# MCU.net
KiCad netlist of a schematic drawn in Altium Designer
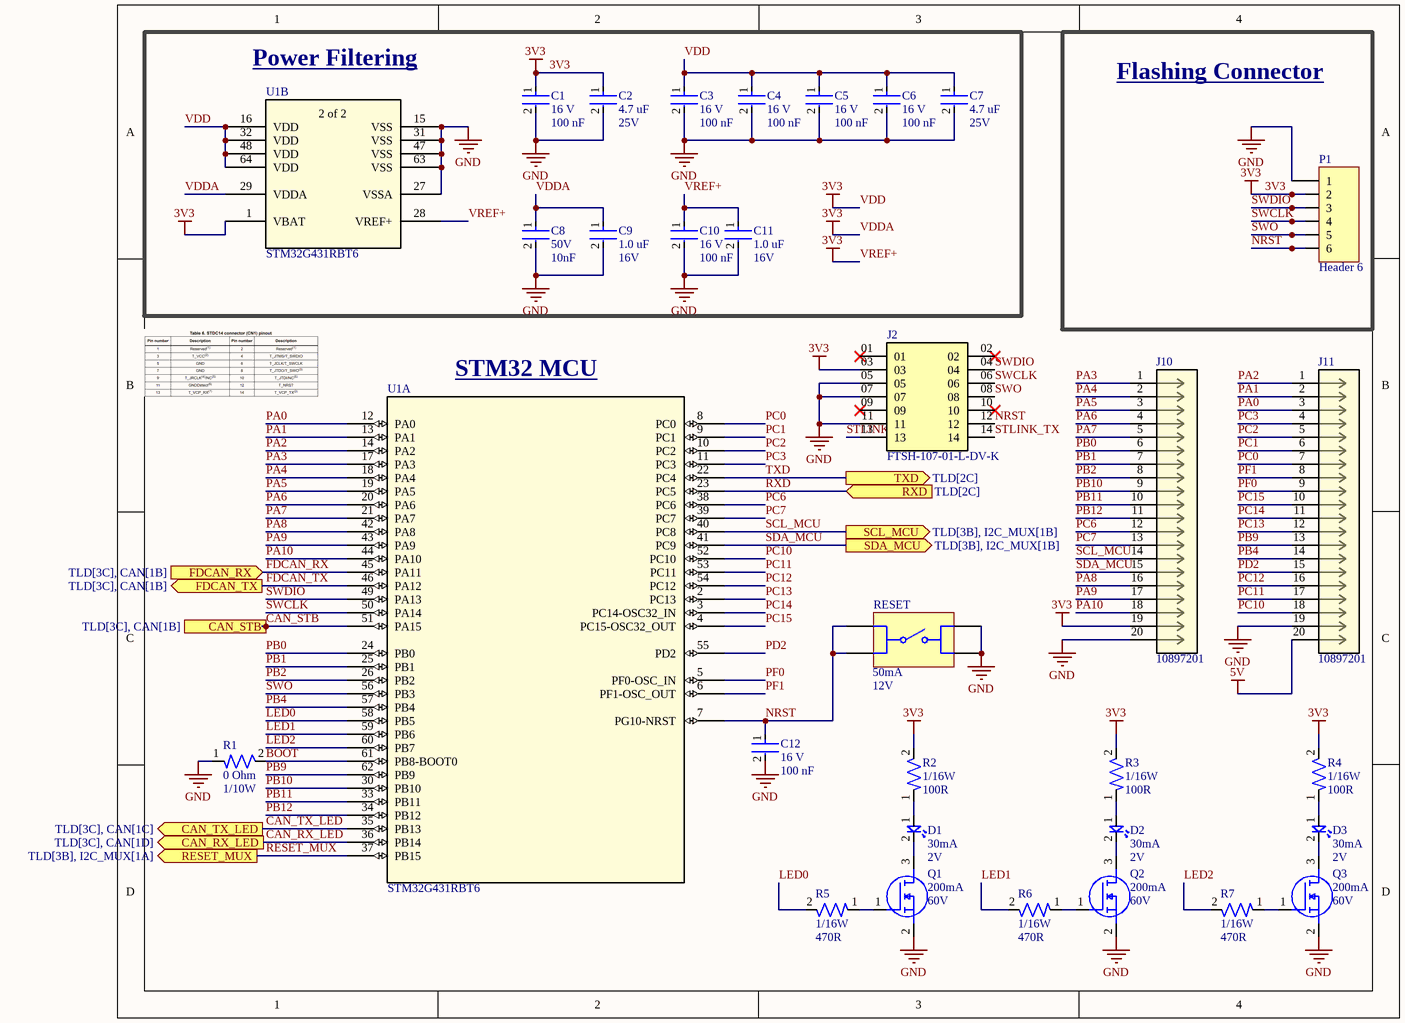
[diagram p0: MCU.SchDoc]

(export (version "E")
  (design (tool "Eeschema 10.0.6"))
  (components
    (comp (ref "C1")
      (value "CC0402KRX7R7BB104")
      (footprint "CAP-0402")
      (description "CAP CER 0.1UF 16V X7R 0402")
      (fields (field (name "VOLTAGE RATING") "16 V") (field (name "CAPACITANCE") "100 nF"))
      (libsource (lib "JLC_25") (part "CAP-0.1U-0001"))
    )
    (comp (ref "C2")
      (value "CC0603KRX5R8BB475")
      (footprint "CAP-0603")
      (description "CAP CER 4.7UF 25V X5R 0603")
      (fields (field (name "CAPACITANCE") "4.7 uF") (field (name "VOLTAGE") "25V"))
      (libsource (lib "JLC_25") (part "CAP-4.7U-0001"))
    )
    (comp (ref "C3")
      (value "CC0402KRX7R7BB104")
      (footprint "CAP-0402")
      (description "CAP CER 0.1UF 16V X7R 0402")
      (fields (field (name "VOLTAGE RATING") "16 V") (field (name "CAPACITANCE") "100 nF"))
      (libsource (lib "JLC_25") (part "CAP-0.1U-0001"))
    )
    (comp (ref "C4")
      (value "CC0402KRX7R7BB104")
      (footprint "CAP-0402")
      (description "CAP CER 0.1UF 16V X7R 0402")
      (fields (field (name "VOLTAGE RATING") "16 V") (field (name "CAPACITANCE") "100 nF"))
      (libsource (lib "JLC_25") (part "CAP-0.1U-0001"))
    )
    (comp (ref "C5")
      (value "CC0402KRX7R7BB104")
      (footprint "CAP-0402")
      (description "CAP CER 0.1UF 16V X7R 0402")
      (fields (field (name "VOLTAGE RATING") "16 V") (field (name "CAPACITANCE") "100 nF"))
      (libsource (lib "JLC_25") (part "CAP-0.1U-0001"))
    )
    (comp (ref "C6")
      (value "CC0402KRX7R7BB104")
      (footprint "CAP-0402")
      (description "CAP CER 0.1UF 16V X7R 0402")
      (fields (field (name "VOLTAGE RATING") "16 V") (field (name "CAPACITANCE") "100 nF"))
      (libsource (lib "JLC_25") (part "CAP-0.1U-0001"))
    )
    (comp (ref "C7")
      (value "CC0603KRX5R8BB475")
      (footprint "CAP-0603")
      (description "CAP CER 4.7UF 25V X5R 0603")
      (fields (field (name "CAPACITANCE") "4.7 uF") (field (name "VOLTAGE") "25V"))
      (libsource (lib "JLC_25") (part "CAP-4.7U-0001"))
    )
    (comp (ref "C8")
      (value "GRM2195C1H103JA01D")
      (footprint "CAP-0805")
      (description "CAP CER 10000PF 50V C0G/NP0 0805")
      (fields (field (name "VOLTAGE") "50V") (field (name "CAPACITANCE") "10nF"))
      (libsource (lib "JLC_25") (part "CAP-10N-0001"))
    )
    (comp (ref "C9")
      (value "CC0603KRX7R7BB105")
      (footprint "CAP-0603")
      (description "CAP CER 1UF 16V X7R 0603")
      (fields (field (name "CAPACITANCE") "1.0 uF") (field (name "VOLTAGE") "16V"))
      (libsource (lib "JLC_25") (part "CAP-1U-0002"))
    )
    (comp (ref "C10")
      (value "CC0402KRX7R7BB104")
      (footprint "CAP-0402")
      (description "CAP CER 0.1UF 16V X7R 0402")
      (fields (field (name "VOLTAGE RATING") "16 V") (field (name "CAPACITANCE") "100 nF"))
      (libsource (lib "JLC_25") (part "CAP-0.1U-0001"))
    )
    (comp (ref "C11")
      (value "CC0603KRX7R7BB105")
      (footprint "CAP-0603")
      (description "CAP CER 1UF 16V X7R 0603")
      (fields (field (name "CAPACITANCE") "1.0 uF") (field (name "VOLTAGE") "16V"))
      (libsource (lib "JLC_25") (part "CAP-1U-0002"))
    )
    (comp (ref "C12")
      (value "CC0402KRX7R7BB104")
      (footprint "CAP-0402")
      (description "CAP CER 0.1UF 16V X7R 0402")
      (fields (field (name "VOLTAGE RATING") "16 V") (field (name "CAPACITANCE") "100 nF"))
      (libsource (lib "JLC_25") (part "CAP-0.1U-0001"))
    )
    (comp (ref "D1")
      (value "BL-HKC36G-AV-TRB")
      (footprint "LED-0603")
      (description "LED YELLOW CLEAR 0603 SMD")
      (fields (field (name "FORWARD CURRENT") "30mA") (field (name "FORWARD VOLTAGE") "2V"))
      (libsource (lib "JLC_25") (part "LED-0001"))
    )
    (comp (ref "D2")
      (value "BL-HKC36G-AV-TRB")
      (footprint "LED-0603")
      (description "LED YELLOW CLEAR 0603 SMD")
      (fields (field (name "FORWARD CURRENT") "30mA") (field (name "FORWARD VOLTAGE") "2V"))
      (libsource (lib "JLC_25") (part "LED-0001"))
    )
    (comp (ref "D3")
      (value "BL-HKC36G-AV-TRB")
      (footprint "LED-0603")
      (description "LED YELLOW CLEAR 0603 SMD")
      (fields (field (name "FORWARD CURRENT") "30mA") (field (name "FORWARD VOLTAGE") "2V"))
      (libsource (lib "JLC_25") (part "LED-0001"))
    )
    (comp (ref "J2")
      (value "FTSH-107-01-L-DV-K")
      (footprint "SAMTEC_FTSH-107-01-L-DV-K")
      (description "Connector Header Surface Mount 14 position 0.050\" (1.27mm)")
      (fields (field (name "MF") "Samtec"))
      (libsource (lib "MasterLib") (part "CONN_Flashing-0001"))
    )
    (comp (ref "J10")
      (value "10897201")
      (footprint "CONN20_0010897201_MOL")
      (fields (field (name "COPYRIGHT") "Copyright (C) 2025 Ultra Librarian. All rights reserved."))
      (libsource (lib "MasterLib") (part "CONN-20"))
    )
    (comp (ref "J11")
      (value "10897201")
      (footprint "CONN20_0010897201_MOL")
      (fields (field (name "COPYRIGHT") "Copyright (C) 2025 Ultra Librarian. All rights reserved."))
      (libsource (lib "MasterLib") (part "CONN-20"))
    )
    (comp (ref "P1")
      (value "Header 6")
      (footprint "HDR1X6")
      (description "Header, 6-Pin")
      (fields (field (name "PUBLISHER") "Altium Limited"))
      (libsource (lib "Miscellaneous Connectors") (part "Header 6"))
    )
    (comp (ref "Q1")
      (value "T2N7002AK,LM")
      (footprint "IC-SOT23-3")
      (description "MOSFET N-CH 60V 200MA SOT23")
      (fields (field (name "CONTINUOUS CURRENT") "200mA") (field (name "VOLTAGE") "60V"))
      (libsource (lib "JLC_25") (part "NMOS-200MA-0001"))
    )
    (comp (ref "Q2")
      (value "T2N7002AK,LM")
      (footprint "IC-SOT23-3")
      (description "MOSFET N-CH 60V 200MA SOT23")
      (fields (field (name "CONTINUOUS CURRENT") "200mA") (field (name "VOLTAGE") "60V"))
      (libsource (lib "JLC_25") (part "NMOS-200MA-0001"))
    )
    (comp (ref "Q3")
      (value "T2N7002AK,LM")
      (footprint "IC-SOT23-3")
      (description "MOSFET N-CH 60V 200MA SOT23")
      (fields (field (name "CONTINUOUS CURRENT") "200mA") (field (name "VOLTAGE") "60V"))
      (libsource (lib "JLC_25") (part "NMOS-200MA-0001"))
    )
    (comp (ref "R1")
      (value "RESC1607X60N")
      (footprint "RESC1607X60N")
      (description "0 Ohms Jumper Chip Resistor 0603 (1608 Metric) Moisture Resistant Thick Film")
      (fields
        (field (name "JLC PART NUMBER") "C106231")
        (field (name "RESISTANCE") "0 Ohm")
        (field (name "POWER") "1/10W")
      )
      (libsource (lib "MasterLib") (part "RES-0-0003"))
    )
    (comp (ref "R2")
      (value "RC0402FR-07100RL")
      (footprint "RES-0402")
      (description "RES 100 OHM 1% 1/16W 0402")
      (fields
        (field (name "TOLERANCE") "1%")
        (field (name "POWER") "1/16W")
        (field (name "RESISTANCE") "100R")
      )
      (libsource (lib "JLC_25") (part "RES-100-0001"))
    )
    (comp (ref "R3")
      (value "RC0402FR-07100RL")
      (footprint "RES-0402")
      (description "RES 100 OHM 1% 1/16W 0402")
      (fields
        (field (name "TOLERANCE") "1%")
        (field (name "POWER") "1/16W")
        (field (name "RESISTANCE") "100R")
      )
      (libsource (lib "JLC_25") (part "RES-100-0001"))
    )
    (comp (ref "R4")
      (value "RC0402FR-07100RL")
      (footprint "RES-0402")
      (description "RES 100 OHM 1% 1/16W 0402")
      (fields
        (field (name "TOLERANCE") "1%")
        (field (name "POWER") "1/16W")
        (field (name "RESISTANCE") "100R")
      )
      (libsource (lib "JLC_25") (part "RES-100-0001"))
    )
    (comp (ref "R5")
      (value "RC0402FR-07470RL")
      (footprint "RES-0402")
      (description "RES 470 OHM 1% 1/16W 0402")
      (fields
        (field (name "TOLERANCE") "1%")
        (field (name "POWER") "1/16W")
        (field (name "RESISTANCE") "470R")
      )
      (libsource (lib "JLC_25") (part "RES-470-0001"))
    )
    (comp (ref "R6")
      (value "RC0402FR-07470RL")
      (footprint "RES-0402")
      (description "RES 470 OHM 1% 1/16W 0402")
      (fields
        (field (name "TOLERANCE") "1%")
        (field (name "POWER") "1/16W")
        (field (name "RESISTANCE") "470R")
      )
      (libsource (lib "JLC_25") (part "RES-470-0001"))
    )
    (comp (ref "R7")
      (value "RC0402FR-07470RL")
      (footprint "RES-0402")
      (description "RES 470 OHM 1% 1/16W 0402")
      (fields
        (field (name "TOLERANCE") "1%")
        (field (name "POWER") "1/16W")
        (field (name "RESISTANCE") "470R")
      )
      (libsource (lib "JLC_25") (part "RES-470-0001"))
    )
    (comp (ref "RESET")
      (value "430182095816")
      (footprint "430182095816")
      (description "WS-TASV SMT Tact Switch, 6mm x 6mm, 160gf, SPST-NO, 12V, 50mA")
      (fields
        (field (name "MANUFACTURER") "Wurth Elektronik")
        (field (name "RATED CURRENT") "50mA")
        (field (name "RATED VOLTAGE (DC)") "12V")
      )
      (libsource (lib "MasterLib") (part "BUTTON-VERT-12V-0.5A"))
    )
    (comp (ref "U1")
      (value "STM32G431RBT6")
      (footprint "LQFP64-10x10mm")
      (fields (field (name "COPYRIGHT") "Copyright (C) 2025 Ultra Librarian. All rights reserved."))
      (libsource (lib "JLC_25") (part "IC-STM32G431RBT6"))
    )
  )
  (nets
    (net (code "1") (name "/BOOT") (class "Default")
      (node (ref "R1") (pin "2") (pinfunction "2_2") (pintype "passive"))
      (node (ref "U1") (pin "61") (pinfunction "PB8-BOOT0_61") (pintype "bidirectional"))
    )
    (net (code "2") (name "/CAN_RX_LED") (class "Default")
      (node (ref "U1") (pin "36") (pinfunction "PB14_36") (pintype "bidirectional"))
    )
    (net (code "3") (name "/CAN_STB") (class "Default")
      (node (ref "U1") (pin "51") (pinfunction "PA15_51") (pintype "bidirectional"))
    )
    (net (code "4") (name "/CAN_TX_LED") (class "Default")
      (node (ref "U1") (pin "35") (pinfunction "PB13_35") (pintype "bidirectional"))
    )
    (net (code "5") (name "/FDCAN_RX") (class "Default")
      (node (ref "U1") (pin "45") (pinfunction "PA11_45") (pintype "bidirectional"))
    )
    (net (code "6") (name "/FDCAN_TX") (class "Default")
      (node (ref "U1") (pin "46") (pinfunction "PA12_46") (pintype "bidirectional"))
    )
    (net (code "7") (name "/LED0") (class "Default")
      (node (ref "R5") (pin "2") (pinfunction "2_2") (pintype "passive"))
      (node (ref "U1") (pin "58") (pinfunction "PB5_58") (pintype "bidirectional"))
    )
    (net (code "8") (name "/LED1") (class "Default")
      (node (ref "R6") (pin "2") (pinfunction "2_2") (pintype "passive"))
      (node (ref "U1") (pin "59") (pinfunction "PB6_59") (pintype "bidirectional"))
    )
    (net (code "9") (name "/LED2") (class "Default")
      (node (ref "R7") (pin "2") (pinfunction "2_2") (pintype "passive"))
      (node (ref "U1") (pin "60") (pinfunction "PB7_60") (pintype "bidirectional"))
    )
    (net (code "10") (name "/NRST") (class "Default")
      (node (ref "C12") (pin "1") (pinfunction "1_1") (pintype "passive"))
      (node (ref "J2") (pin "12") (pinfunction "12_12") (pintype "passive"))
      (node (ref "P1") (pin "6") (pinfunction "6_6") (pintype "passive"))
      (node (ref "RESET") (pin "A1") (pinfunction "A1_A1") (pintype "passive"))
      (node (ref "RESET") (pin "A2") (pinfunction "A2_A2") (pintype "passive"))
      (node (ref "U1") (pin "7") (pinfunction "PG10-NRST_7") (pintype "bidirectional"))
    )
    (net (code "11") (name "/PA0") (class "Default")
      (node (ref "J11") (pin "3") (pinfunction "3_3") (pintype "passive"))
      (node (ref "U1") (pin "12") (pinfunction "PA0_12") (pintype "bidirectional"))
    )
    (net (code "12") (name "/PA1") (class "Default")
      (node (ref "J11") (pin "2") (pinfunction "2_2") (pintype "passive"))
      (node (ref "U1") (pin "13") (pinfunction "PA1_13") (pintype "bidirectional"))
    )
    (net (code "13") (name "/PA2") (class "Default")
      (node (ref "J11") (pin "1") (pinfunction "1_1") (pintype "passive"))
      (node (ref "U1") (pin "14") (pinfunction "PA2_14") (pintype "bidirectional"))
    )
    (net (code "14") (name "/PA3") (class "Default")
      (node (ref "J10") (pin "1") (pinfunction "1_1") (pintype "passive"))
      (node (ref "U1") (pin "17") (pinfunction "PA3_17") (pintype "bidirectional"))
    )
    (net (code "15") (name "/PA4") (class "Default")
      (node (ref "J10") (pin "2") (pinfunction "2_2") (pintype "passive"))
      (node (ref "U1") (pin "18") (pinfunction "PA4_18") (pintype "bidirectional"))
    )
    (net (code "16") (name "/PA5") (class "Default")
      (node (ref "J10") (pin "3") (pinfunction "3_3") (pintype "passive"))
      (node (ref "U1") (pin "19") (pinfunction "PA5_19") (pintype "bidirectional"))
    )
    (net (code "17") (name "/PA6") (class "Default")
      (node (ref "J10") (pin "4") (pinfunction "4_4") (pintype "passive"))
      (node (ref "U1") (pin "20") (pinfunction "PA6_20") (pintype "bidirectional"))
    )
    (net (code "18") (name "/PA7") (class "Default")
      (node (ref "J10") (pin "5") (pinfunction "5_5") (pintype "passive"))
      (node (ref "U1") (pin "21") (pinfunction "PA7_21") (pintype "bidirectional"))
    )
    (net (code "19") (name "/PA8") (class "Default")
      (node (ref "J10") (pin "16") (pinfunction "16_16") (pintype "passive"))
      (node (ref "U1") (pin "42") (pinfunction "PA8_42") (pintype "bidirectional"))
    )
    (net (code "20") (name "/PA9") (class "Default")
      (node (ref "J10") (pin "17") (pinfunction "17_17") (pintype "passive"))
      (node (ref "U1") (pin "43") (pinfunction "PA9_43") (pintype "bidirectional"))
    )
    (net (code "21") (name "/PA10") (class "Default")
      (node (ref "J10") (pin "18") (pinfunction "18_18") (pintype "passive"))
      (node (ref "U1") (pin "44") (pinfunction "PA10_44") (pintype "bidirectional"))
    )
    (net (code "22") (name "/PB0") (class "Default")
      (node (ref "J10") (pin "6") (pinfunction "6_6") (pintype "passive"))
      (node (ref "U1") (pin "24") (pinfunction "PB0_24") (pintype "bidirectional"))
    )
    (net (code "23") (name "/PB1") (class "Default")
      (node (ref "J10") (pin "7") (pinfunction "7_7") (pintype "passive"))
      (node (ref "U1") (pin "25") (pinfunction "PB1_25") (pintype "bidirectional"))
    )
    (net (code "24") (name "/PB2") (class "Default")
      (node (ref "J10") (pin "8") (pinfunction "8_8") (pintype "passive"))
      (node (ref "U1") (pin "26") (pinfunction "PB2_26") (pintype "bidirectional"))
    )
    (net (code "25") (name "/PB4") (class "Default")
      (node (ref "J11") (pin "14") (pinfunction "14_14") (pintype "passive"))
      (node (ref "U1") (pin "57") (pinfunction "PB4_57") (pintype "bidirectional"))
    )
    (net (code "26") (name "/PB9") (class "Default")
      (node (ref "J11") (pin "13") (pinfunction "13_13") (pintype "passive"))
      (node (ref "U1") (pin "62") (pinfunction "PB9_62") (pintype "bidirectional"))
    )
    (net (code "27") (name "/PB10") (class "Default")
      (node (ref "J10") (pin "9") (pinfunction "9_9") (pintype "passive"))
      (node (ref "U1") (pin "30") (pinfunction "PB10_30") (pintype "bidirectional"))
    )
    (net (code "28") (name "/PB11") (class "Default")
      (node (ref "J10") (pin "10") (pinfunction "10_10") (pintype "passive"))
      (node (ref "U1") (pin "33") (pinfunction "PB11_33") (pintype "bidirectional"))
    )
    (net (code "29") (name "/PB12") (class "Default")
      (node (ref "J10") (pin "11") (pinfunction "11_11") (pintype "passive"))
      (node (ref "U1") (pin "34") (pinfunction "PB12_34") (pintype "bidirectional"))
    )
    (net (code "30") (name "/PC0") (class "Default")
      (node (ref "J11") (pin "7") (pinfunction "7_7") (pintype "passive"))
      (node (ref "U1") (pin "8") (pinfunction "PC0_8") (pintype "bidirectional"))
    )
    (net (code "31") (name "/PC1") (class "Default")
      (node (ref "J11") (pin "6") (pinfunction "6_6") (pintype "passive"))
      (node (ref "U1") (pin "9") (pinfunction "PC1_9") (pintype "bidirectional"))
    )
    (net (code "32") (name "/PC2") (class "Default")
      (node (ref "J11") (pin "5") (pinfunction "5_5") (pintype "passive"))
      (node (ref "U1") (pin "10") (pinfunction "PC2_10") (pintype "bidirectional"))
    )
    (net (code "33") (name "/PC3") (class "Default")
      (node (ref "J11") (pin "4") (pinfunction "4_4") (pintype "passive"))
      (node (ref "U1") (pin "11") (pinfunction "PC3_11") (pintype "bidirectional"))
    )
    (net (code "34") (name "/PC6") (class "Default")
      (node (ref "J10") (pin "12") (pinfunction "12_12") (pintype "passive"))
      (node (ref "U1") (pin "38") (pinfunction "PC6_38") (pintype "bidirectional"))
    )
    (net (code "35") (name "/PC7") (class "Default")
      (node (ref "J10") (pin "13") (pinfunction "13_13") (pintype "passive"))
      (node (ref "U1") (pin "39") (pinfunction "PC7_39") (pintype "bidirectional"))
    )
    (net (code "36") (name "/PC10") (class "Default")
      (node (ref "J11") (pin "18") (pinfunction "18_18") (pintype "passive"))
      (node (ref "U1") (pin "52") (pinfunction "PC10_52") (pintype "bidirectional"))
    )
    (net (code "37") (name "/PC11") (class "Default")
      (node (ref "J11") (pin "17") (pinfunction "17_17") (pintype "passive"))
      (node (ref "U1") (pin "53") (pinfunction "PC11_53") (pintype "bidirectional"))
    )
    (net (code "38") (name "/PC12") (class "Default")
      (node (ref "J11") (pin "16") (pinfunction "16_16") (pintype "passive"))
      (node (ref "U1") (pin "54") (pinfunction "PC12_54") (pintype "bidirectional"))
    )
    (net (code "39") (name "/PC13") (class "Default")
      (node (ref "J11") (pin "12") (pinfunction "12_12") (pintype "passive"))
      (node (ref "U1") (pin "2") (pinfunction "PC13_2") (pintype "bidirectional"))
    )
    (net (code "40") (name "/PC14") (class "Default")
      (node (ref "J11") (pin "11") (pinfunction "11_11") (pintype "passive"))
      (node (ref "U1") (pin "3") (pinfunction "PC14-OSC32_IN_3") (pintype "bidirectional"))
    )
    (net (code "41") (name "/PC15") (class "Default")
      (node (ref "J11") (pin "10") (pinfunction "10_10") (pintype "passive"))
      (node (ref "U1") (pin "4") (pinfunction "PC15-OSC32_OUT_4") (pintype "bidirectional"))
    )
    (net (code "42") (name "/PD2") (class "Default")
      (node (ref "J11") (pin "15") (pinfunction "15_15") (pintype "passive"))
      (node (ref "U1") (pin "55") (pinfunction "PD2_55") (pintype "bidirectional"))
    )
    (net (code "43") (name "/PF0") (class "Default")
      (node (ref "J11") (pin "9") (pinfunction "9_9") (pintype "passive"))
      (node (ref "U1") (pin "5") (pinfunction "PF0-OSC_IN_5") (pintype "bidirectional"))
    )
    (net (code "44") (name "/PF1") (class "Default")
      (node (ref "J11") (pin "8") (pinfunction "8_8") (pintype "passive"))
      (node (ref "U1") (pin "6") (pinfunction "PF1-OSC_OUT_6") (pintype "bidirectional"))
    )
    (net (code "45") (name "/RESET_MUX") (class "Default")
      (node (ref "U1") (pin "37") (pinfunction "PB15_37") (pintype "bidirectional"))
    )
    (net (code "46") (name "/RXD") (class "Default")
      (node (ref "U1") (pin "23") (pinfunction "PC5_23") (pintype "bidirectional"))
    )
    (net (code "47") (name "/SCL_MCU") (class "Default")
      (node (ref "J10") (pin "14") (pinfunction "14_14") (pintype "passive"))
      (node (ref "U1") (pin "40") (pinfunction "PC8_40") (pintype "bidirectional"))
    )
    (net (code "48") (name "/SDA_MCU") (class "Default")
      (node (ref "J10") (pin "15") (pinfunction "15_15") (pintype "passive"))
      (node (ref "U1") (pin "41") (pinfunction "PC9_41") (pintype "bidirectional"))
    )
    (net (code "49") (name "/STLINK_RX") (class "Default")
      (node (ref "J2") (pin "13") (pinfunction "13_13") (pintype "passive"))
    )
    (net (code "50") (name "/STLINK_TX") (class "Default")
      (node (ref "J2") (pin "14") (pinfunction "14_14") (pintype "passive"))
    )
    (net (code "51") (name "/SWCLK") (class "Default")
      (node (ref "J2") (pin "06") (pinfunction "06_06") (pintype "passive"))
      (node (ref "P1") (pin "4") (pinfunction "4_4") (pintype "passive"))
      (node (ref "U1") (pin "50") (pinfunction "PA14_50") (pintype "bidirectional"))
    )
    (net (code "52") (name "/SWDIO") (class "Default")
      (node (ref "J2") (pin "04") (pinfunction "04_04") (pintype "passive"))
      (node (ref "P1") (pin "3") (pinfunction "3_3") (pintype "passive"))
      (node (ref "U1") (pin "49") (pinfunction "PA13_49") (pintype "bidirectional"))
    )
    (net (code "53") (name "/SWO") (class "Default")
      (node (ref "J2") (pin "08") (pinfunction "08_08") (pintype "passive"))
      (node (ref "P1") (pin "5") (pinfunction "5_5") (pintype "passive"))
      (node (ref "U1") (pin "56") (pinfunction "PB3_56") (pintype "bidirectional"))
    )
    (net (code "54") (name "/TXD") (class "Default")
      (node (ref "U1") (pin "22") (pinfunction "PC4_22") (pintype "bidirectional"))
    )
    (net (code "55") (name "3V3") (class "Default")
      (node (ref "C1") (pin "1") (pinfunction "1_1") (pintype "passive"))
      (node (ref "C10") (pin "1") (pinfunction "1_1") (pintype "passive"))
      (node (ref "C11") (pin "1") (pinfunction "1_1") (pintype "passive"))
      (node (ref "C2") (pin "1") (pinfunction "1_1") (pintype "passive"))
      (node (ref "C3") (pin "1") (pinfunction "1_1") (pintype "passive"))
      (node (ref "C4") (pin "1") (pinfunction "1_1") (pintype "passive"))
      (node (ref "C5") (pin "1") (pinfunction "1_1") (pintype "passive"))
      (node (ref "C6") (pin "1") (pinfunction "1_1") (pintype "passive"))
      (node (ref "C7") (pin "1") (pinfunction "1_1") (pintype "passive"))
      (node (ref "C8") (pin "1") (pinfunction "1_1") (pintype "passive"))
      (node (ref "C9") (pin "1") (pinfunction "1_1") (pintype "passive"))
      (node (ref "J10") (pin "19") (pinfunction "19_19") (pintype "passive"))
      (node (ref "J2") (pin "03") (pinfunction "03_03") (pintype "passive"))
      (node (ref "P1") (pin "2") (pinfunction "2_2") (pintype "passive"))
      (node (ref "R2") (pin "2") (pinfunction "2_2") (pintype "passive"))
      (node (ref "R3") (pin "2") (pinfunction "2_2") (pintype "passive"))
      (node (ref "R4") (pin "2") (pinfunction "2_2") (pintype "passive"))
      (node (ref "U1") (pin "1") (pinfunction "VBAT_1") (pintype "power_in"))
      (node (ref "U1") (pin "16") (pinfunction "VDD_16") (pintype "power_in"))
      (node (ref "U1") (pin "28") (pinfunction "VREF+_28") (pintype "power_in"))
      (node (ref "U1") (pin "29") (pinfunction "VDDA_29") (pintype "power_in"))
      (node (ref "U1") (pin "32") (pinfunction "VDD_32") (pintype "power_in"))
      (node (ref "U1") (pin "48") (pinfunction "VDD_48") (pintype "power_in"))
      (node (ref "U1") (pin "64") (pinfunction "VDD_64") (pintype "power_in"))
    )
    (net (code "56") (name "5V") (class "Default")
      (node (ref "J11") (pin "20") (pinfunction "20_20") (pintype "passive"))
    )
    (net (code "57") (name "GND") (class "Default")
      (node (ref "C1") (pin "2") (pinfunction "2_2") (pintype "passive"))
      (node (ref "C10") (pin "2") (pinfunction "2_2") (pintype "passive"))
      (node (ref "C11") (pin "2") (pinfunction "2_2") (pintype "passive"))
      (node (ref "C12") (pin "2") (pinfunction "2_2") (pintype "passive"))
      (node (ref "C2") (pin "2") (pinfunction "2_2") (pintype "passive"))
      (node (ref "C3") (pin "2") (pinfunction "2_2") (pintype "passive"))
      (node (ref "C4") (pin "2") (pinfunction "2_2") (pintype "passive"))
      (node (ref "C5") (pin "2") (pinfunction "2_2") (pintype "passive"))
      (node (ref "C6") (pin "2") (pinfunction "2_2") (pintype "passive"))
      (node (ref "C7") (pin "2") (pinfunction "2_2") (pintype "passive"))
      (node (ref "C8") (pin "2") (pinfunction "2_2") (pintype "passive"))
      (node (ref "C9") (pin "2") (pinfunction "2_2") (pintype "passive"))
      (node (ref "J10") (pin "20") (pinfunction "20_20") (pintype "passive"))
      (node (ref "J11") (pin "19") (pinfunction "19_19") (pintype "passive"))
      (node (ref "J2") (pin "05") (pinfunction "05_05") (pintype "passive"))
      (node (ref "J2") (pin "07") (pinfunction "07_07") (pintype "passive"))
      (node (ref "J2") (pin "11") (pinfunction "11_11") (pintype "passive"))
      (node (ref "P1") (pin "1") (pinfunction "1_1") (pintype "passive"))
      (node (ref "Q1") (pin "2") (pinfunction "S_2") (pintype "passive"))
      (node (ref "Q2") (pin "2") (pinfunction "S_2") (pintype "passive"))
      (node (ref "Q3") (pin "2") (pinfunction "S_2") (pintype "passive"))
      (node (ref "R1") (pin "1") (pinfunction "1_1") (pintype "passive"))
      (node (ref "RESET") (pin "B1") (pinfunction "B1_B1") (pintype "passive"))
      (node (ref "RESET") (pin "B2") (pinfunction "B2_B2") (pintype "passive"))
      (node (ref "U1") (pin "15") (pinfunction "VSS_15") (pintype "power_in"))
      (node (ref "U1") (pin "27") (pinfunction "VSSA_27") (pintype "power_in"))
      (node (ref "U1") (pin "31") (pinfunction "VSS_31") (pintype "power_in"))
      (node (ref "U1") (pin "47") (pinfunction "VSS_47") (pintype "power_in"))
      (node (ref "U1") (pin "63") (pinfunction "VSS_63") (pintype "power_in"))
    )
    (net (code "58") (name "Net-(D1-Pad1)") (class "Default")
      (node (ref "D1") (pin "1") (pinfunction "1_1") (pintype "passive"))
      (node (ref "R2") (pin "1") (pinfunction "1_1") (pintype "passive"))
    )
    (net (code "59") (name "Net-(D2-Pad1)") (class "Default")
      (node (ref "D2") (pin "1") (pinfunction "1_1") (pintype "passive"))
      (node (ref "R3") (pin "1") (pinfunction "1_1") (pintype "passive"))
    )
    (net (code "60") (name "Net-(D3-Pad1)") (class "Default")
      (node (ref "D3") (pin "1") (pinfunction "1_1") (pintype "passive"))
      (node (ref "R4") (pin "1") (pinfunction "1_1") (pintype "passive"))
    )
    (net (code "61") (name "Net-(Q1-D)") (class "Default")
      (node (ref "D1") (pin "2") (pinfunction "2_2") (pintype "passive"))
      (node (ref "Q1") (pin "3") (pinfunction "D_3") (pintype "passive"))
    )
    (net (code "62") (name "Net-(Q1-G)") (class "Default")
      (node (ref "Q1") (pin "1") (pinfunction "G_1") (pintype "passive"))
      (node (ref "R5") (pin "1") (pinfunction "1_1") (pintype "passive"))
    )
    (net (code "63") (name "Net-(Q2-D)") (class "Default")
      (node (ref "D2") (pin "2") (pinfunction "2_2") (pintype "passive"))
      (node (ref "Q2") (pin "3") (pinfunction "D_3") (pintype "passive"))
    )
    (net (code "64") (name "Net-(Q2-G)") (class "Default")
      (node (ref "Q2") (pin "1") (pinfunction "G_1") (pintype "passive"))
      (node (ref "R6") (pin "1") (pinfunction "1_1") (pintype "passive"))
    )
    (net (code "65") (name "Net-(Q3-D)") (class "Default")
      (node (ref "D3") (pin "2") (pinfunction "2_2") (pintype "passive"))
      (node (ref "Q3") (pin "3") (pinfunction "D_3") (pintype "passive"))
    )
    (net (code "66") (name "Net-(Q3-G)") (class "Default")
      (node (ref "Q3") (pin "1") (pinfunction "G_1") (pintype "passive"))
      (node (ref "R7") (pin "1") (pinfunction "1_1") (pintype "passive"))
    )
    (net (code "67") (name "unconnected-(J2-Pad01)") (class "Default")
      (node (ref "J2") (pin "01") (pinfunction "01_01") (pintype "passive+no_connect"))
    )
    (net (code "68") (name "unconnected-(J2-Pad02)") (class "Default")
      (node (ref "J2") (pin "02") (pinfunction "02_02") (pintype "passive+no_connect"))
    )
    (net (code "69") (name "unconnected-(J2-Pad09)") (class "Default")
      (node (ref "J2") (pin "09") (pinfunction "09_09") (pintype "passive+no_connect"))
    )
    (net (code "70") (name "unconnected-(J2-Pad10)") (class "Default")
      (node (ref "J2") (pin "10") (pinfunction "10_10") (pintype "passive+no_connect"))
    )
  )
)
